# ETHERNET.net
KiCad netlist of a schematic drawn in Altium Designer
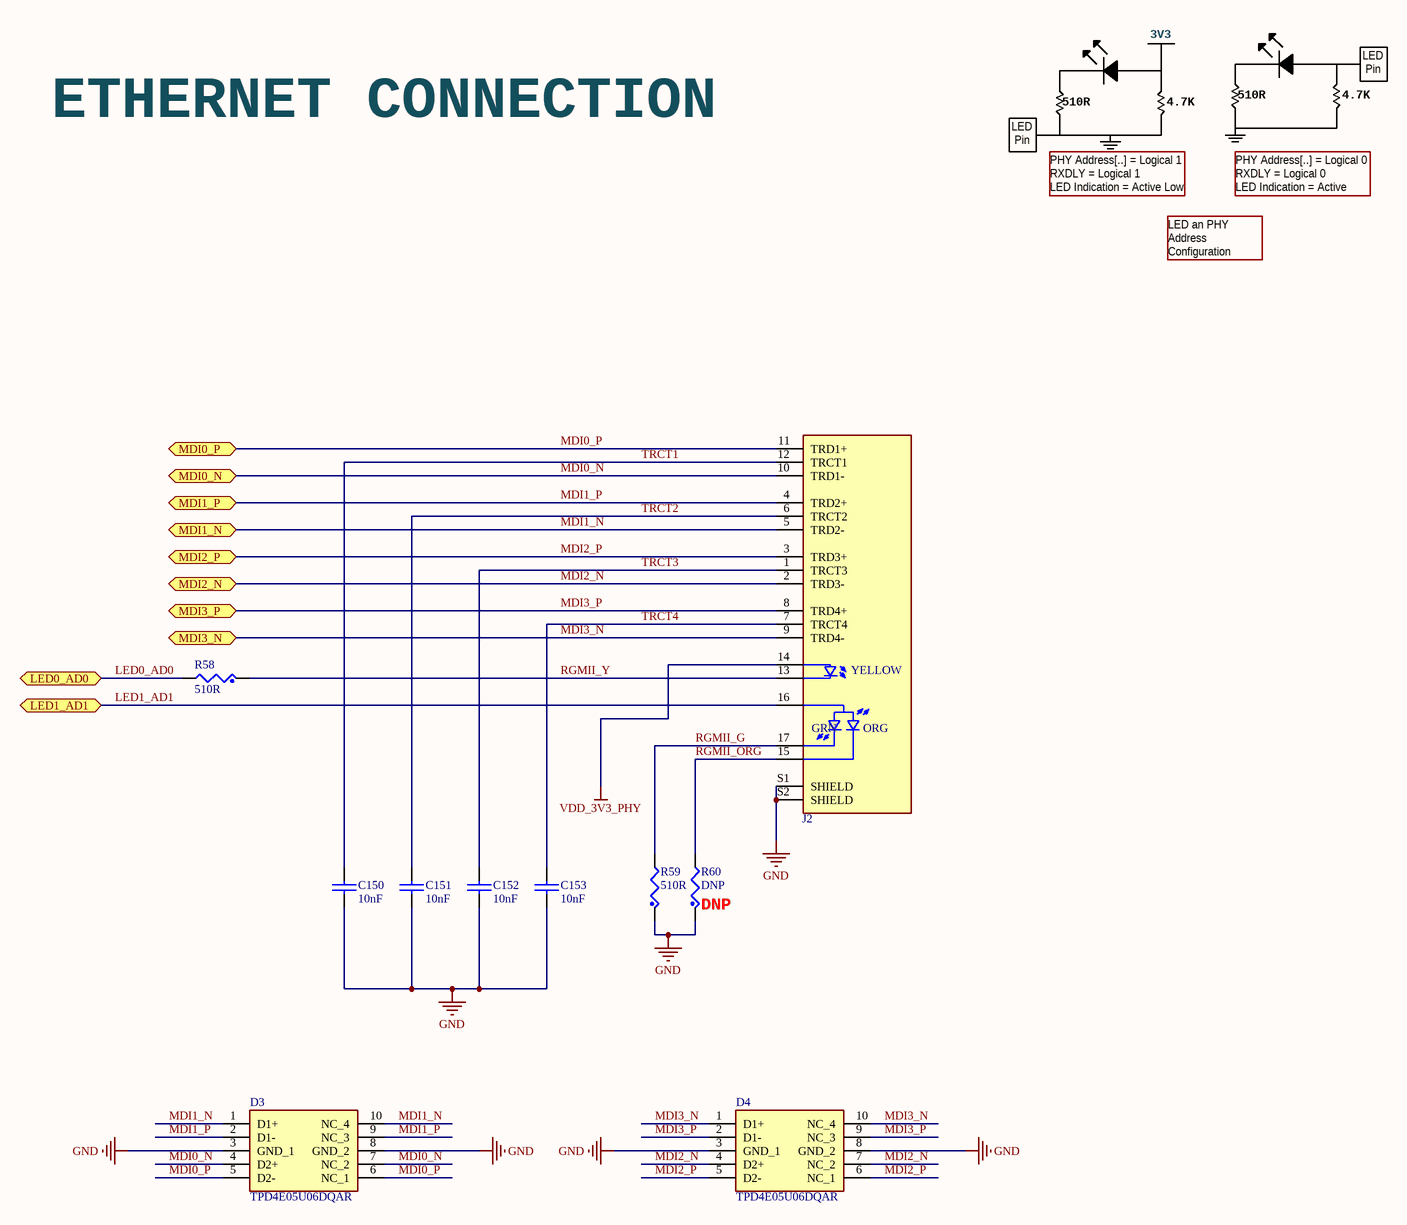
[diagram p0: ETHERNET.SchDoc]

(export (version "E")
  (design (tool "Eeschema 10.0.6"))
  (components
    (comp (ref "C150")
      (value "10nF")
      (footprint "0402_CC - C")
      (libsource (lib "AAR_RockChip_RK3328") (part "CAP_NP"))
    )
    (comp (ref "C151")
      (value "10nF")
      (footprint "0402_CC - C")
      (libsource (lib "AAR_RockChip_RK3328") (part "CAP_NP"))
    )
    (comp (ref "C152")
      (value "10nF")
      (footprint "0402_CC - C")
      (libsource (lib "AAR_RockChip_RK3328") (part "CAP_NP"))
    )
    (comp (ref "C153")
      (value "10nF")
      (footprint "0402_CC - C")
      (libsource (lib "AAR_RockChip_RK3328") (part "CAP_NP"))
    )
    (comp (ref "D3")
      (value "TPD4E05U06DQAR")
      (footprint "DQA(R-PUSON-N10)")
      (description "ESD Suppressors / TVS Diodes 4Chnl U-Lo Capacitnc IEC ESD Prot Diodes")
      (fields (field (name "MFR") "Texas Instruments"))
      (libsource (lib "AAR_RockChip_RK3328") (part "TPD4E05U06DQAR"))
    )
    (comp (ref "D4")
      (value "TPD4E05U06DQAR")
      (footprint "DQA(R-PUSON-N10)")
      (description "ESD Suppressors / TVS Diodes 4Chnl U-Lo Capacitnc IEC ESD Prot Diodes")
      (fields (field (name "MFR") "Texas Instruments"))
      (libsource (lib "AAR_RockChip_RK3328") (part "TPD4E05U06DQAR"))
    )
    (comp (ref "J2")
      (value "L829-1J1T-43")
      (footprint "BEL_L829-1J1T-43")
      (description "MagJack 1000BASE-T ¦ 1X1 ¦ 3w-OG/Y ¦ Tab Up ¦ Low Profile ¦ RoHS")
      (fields (field (name "MFR") "Bel Magnetic Solutions"))
      (libsource (lib "AAR_RockChip_RK3328") (part "L829-1J1T-43"))
    )
    (comp (ref "R58")
      (value "510R")
      (footprint "0402_CR")
      (libsource (lib "AAR_RockChip_RK3328") (part "RES"))
    )
    (comp (ref "R59")
      (value "510R")
      (footprint "0402_CR")
      (libsource (lib "AAR_RockChip_RK3328") (part "RES"))
    )
    (comp (ref "R60")
      (value "DNP")
      (footprint "0402_CR")
      (libsource (lib "AAR_RockChip_RK3328") (part "RES"))
    )
  )
  (nets
    (net (code "1") (name "/LED0_AD0") (class "Default")
      (node (ref "R58") (pin "2") (pinfunction "2_2") (pintype "passive"))
    )
    (net (code "2") (name "/LED1_AD1") (class "Default")
      (node (ref "J2") (pin "16") (pinfunction "CA_16") (pintype "passive"))
    )
    (net (code "3") (name "/MDI0_N") (class "Default")
      (node (ref "D3") (pin "4") (pinfunction "D2+_4") (pintype "passive"))
      (node (ref "D3") (pin "7") (pinfunction "NC_2_7") (pintype "passive"))
      (node (ref "J2") (pin "10") (pinfunction "TRD1-_10") (pintype "passive"))
    )
    (net (code "4") (name "/MDI0_P") (class "Default")
      (node (ref "D3") (pin "5") (pinfunction "D2-_5") (pintype "passive"))
      (node (ref "D3") (pin "6") (pinfunction "NC_1_6") (pintype "passive"))
      (node (ref "J2") (pin "11") (pinfunction "TRD1+_11") (pintype "passive"))
    )
    (net (code "5") (name "/MDI1_N") (class "Default")
      (node (ref "D3") (pin "1") (pinfunction "D1+_1") (pintype "passive"))
      (node (ref "D3") (pin "10") (pinfunction "NC_4_10") (pintype "passive"))
      (node (ref "J2") (pin "5") (pinfunction "TRD2-_5") (pintype "passive"))
    )
    (net (code "6") (name "/MDI1_P") (class "Default")
      (node (ref "D3") (pin "2") (pinfunction "D1-_2") (pintype "passive"))
      (node (ref "D3") (pin "9") (pinfunction "NC_3_9") (pintype "passive"))
      (node (ref "J2") (pin "4") (pinfunction "TRD2+_4") (pintype "passive"))
    )
    (net (code "7") (name "/MDI2_N") (class "Default")
      (node (ref "D4") (pin "4") (pinfunction "D2+_4") (pintype "passive"))
      (node (ref "D4") (pin "7") (pinfunction "NC_2_7") (pintype "passive"))
      (node (ref "J2") (pin "2") (pinfunction "TRD3-_2") (pintype "passive"))
    )
    (net (code "8") (name "/MDI2_P") (class "Default")
      (node (ref "D4") (pin "5") (pinfunction "D2-_5") (pintype "passive"))
      (node (ref "D4") (pin "6") (pinfunction "NC_1_6") (pintype "passive"))
      (node (ref "J2") (pin "3") (pinfunction "TRD3+_3") (pintype "passive"))
    )
    (net (code "9") (name "/MDI3_N") (class "Default")
      (node (ref "D4") (pin "1") (pinfunction "D1+_1") (pintype "passive"))
      (node (ref "D4") (pin "10") (pinfunction "NC_4_10") (pintype "passive"))
      (node (ref "J2") (pin "9") (pinfunction "TRD4-_9") (pintype "passive"))
    )
    (net (code "10") (name "/MDI3_P") (class "Default")
      (node (ref "D4") (pin "2") (pinfunction "D1-_2") (pintype "passive"))
      (node (ref "D4") (pin "9") (pinfunction "NC_3_9") (pintype "passive"))
      (node (ref "J2") (pin "8") (pinfunction "TRD4+_8") (pintype "passive"))
    )
    (net (code "11") (name "/RGMII_G") (class "Default")
      (node (ref "J2") (pin "17") (pinfunction "GK_1_17") (pintype "passive"))
      (node (ref "R59") (pin "2") (pinfunction "2_2") (pintype "passive"))
    )
    (net (code "12") (name "/RGMII_ORG") (class "Default")
      (node (ref "J2") (pin "15") (pinfunction "OK_1_15") (pintype "passive"))
      (node (ref "R60") (pin "2") (pinfunction "2_2") (pintype "passive"))
    )
    (net (code "13") (name "/RGMII_Y") (class "Default")
      (node (ref "J2") (pin "13") (pinfunction "YK_1_13") (pintype "passive"))
      (node (ref "R58") (pin "1") (pinfunction "1_1") (pintype "passive"))
    )
    (net (code "14") (name "/TRCT1") (class "Default")
      (node (ref "C150") (pin "1") (pinfunction "1_1") (pintype "passive"))
      (node (ref "J2") (pin "12") (pinfunction "TRCT1_12") (pintype "passive"))
    )
    (net (code "15") (name "/TRCT2") (class "Default")
      (node (ref "C151") (pin "1") (pinfunction "1_1") (pintype "passive"))
      (node (ref "J2") (pin "6") (pinfunction "TRCT2_6") (pintype "passive"))
    )
    (net (code "16") (name "/TRCT3") (class "Default")
      (node (ref "C152") (pin "1") (pinfunction "1_1") (pintype "passive"))
      (node (ref "J2") (pin "1") (pinfunction "TRCT3_1") (pintype "passive"))
    )
    (net (code "17") (name "/TRCT4") (class "Default")
      (node (ref "C153") (pin "1") (pinfunction "1_1") (pintype "passive"))
      (node (ref "J2") (pin "7") (pinfunction "TRCT4_7") (pintype "passive"))
    )
    (net (code "18") (name "GND") (class "Default")
      (node (ref "C150") (pin "2") (pinfunction "2_2") (pintype "passive"))
      (node (ref "C151") (pin "2") (pinfunction "2_2") (pintype "passive"))
      (node (ref "C152") (pin "2") (pinfunction "2_2") (pintype "passive"))
      (node (ref "C153") (pin "2") (pinfunction "2_2") (pintype "passive"))
      (node (ref "D3") (pin "3") (pinfunction "GND_1_3") (pintype "passive"))
      (node (ref "D3") (pin "8") (pinfunction "GND_2_8") (pintype "passive"))
      (node (ref "D4") (pin "3") (pinfunction "GND_1_3") (pintype "passive"))
      (node (ref "D4") (pin "8") (pinfunction "GND_2_8") (pintype "passive"))
      (node (ref "J2") (pin "S1") (pinfunction "SHIELD_S1") (pintype "passive"))
      (node (ref "J2") (pin "S2") (pinfunction "SHIELD_S2") (pintype "passive"))
      (node (ref "R59") (pin "1") (pinfunction "1_1") (pintype "passive"))
      (node (ref "R60") (pin "1") (pinfunction "1_1") (pintype "passive"))
    )
    (net (code "19") (name "VDD_3V3_PHY") (class "Default")
      (node (ref "J2") (pin "14") (pinfunction "YA_1_14") (pintype "passive"))
    )
  )
)
